# 1_uC.net
KiCad netlist of a schematic drawn in Altium Designer
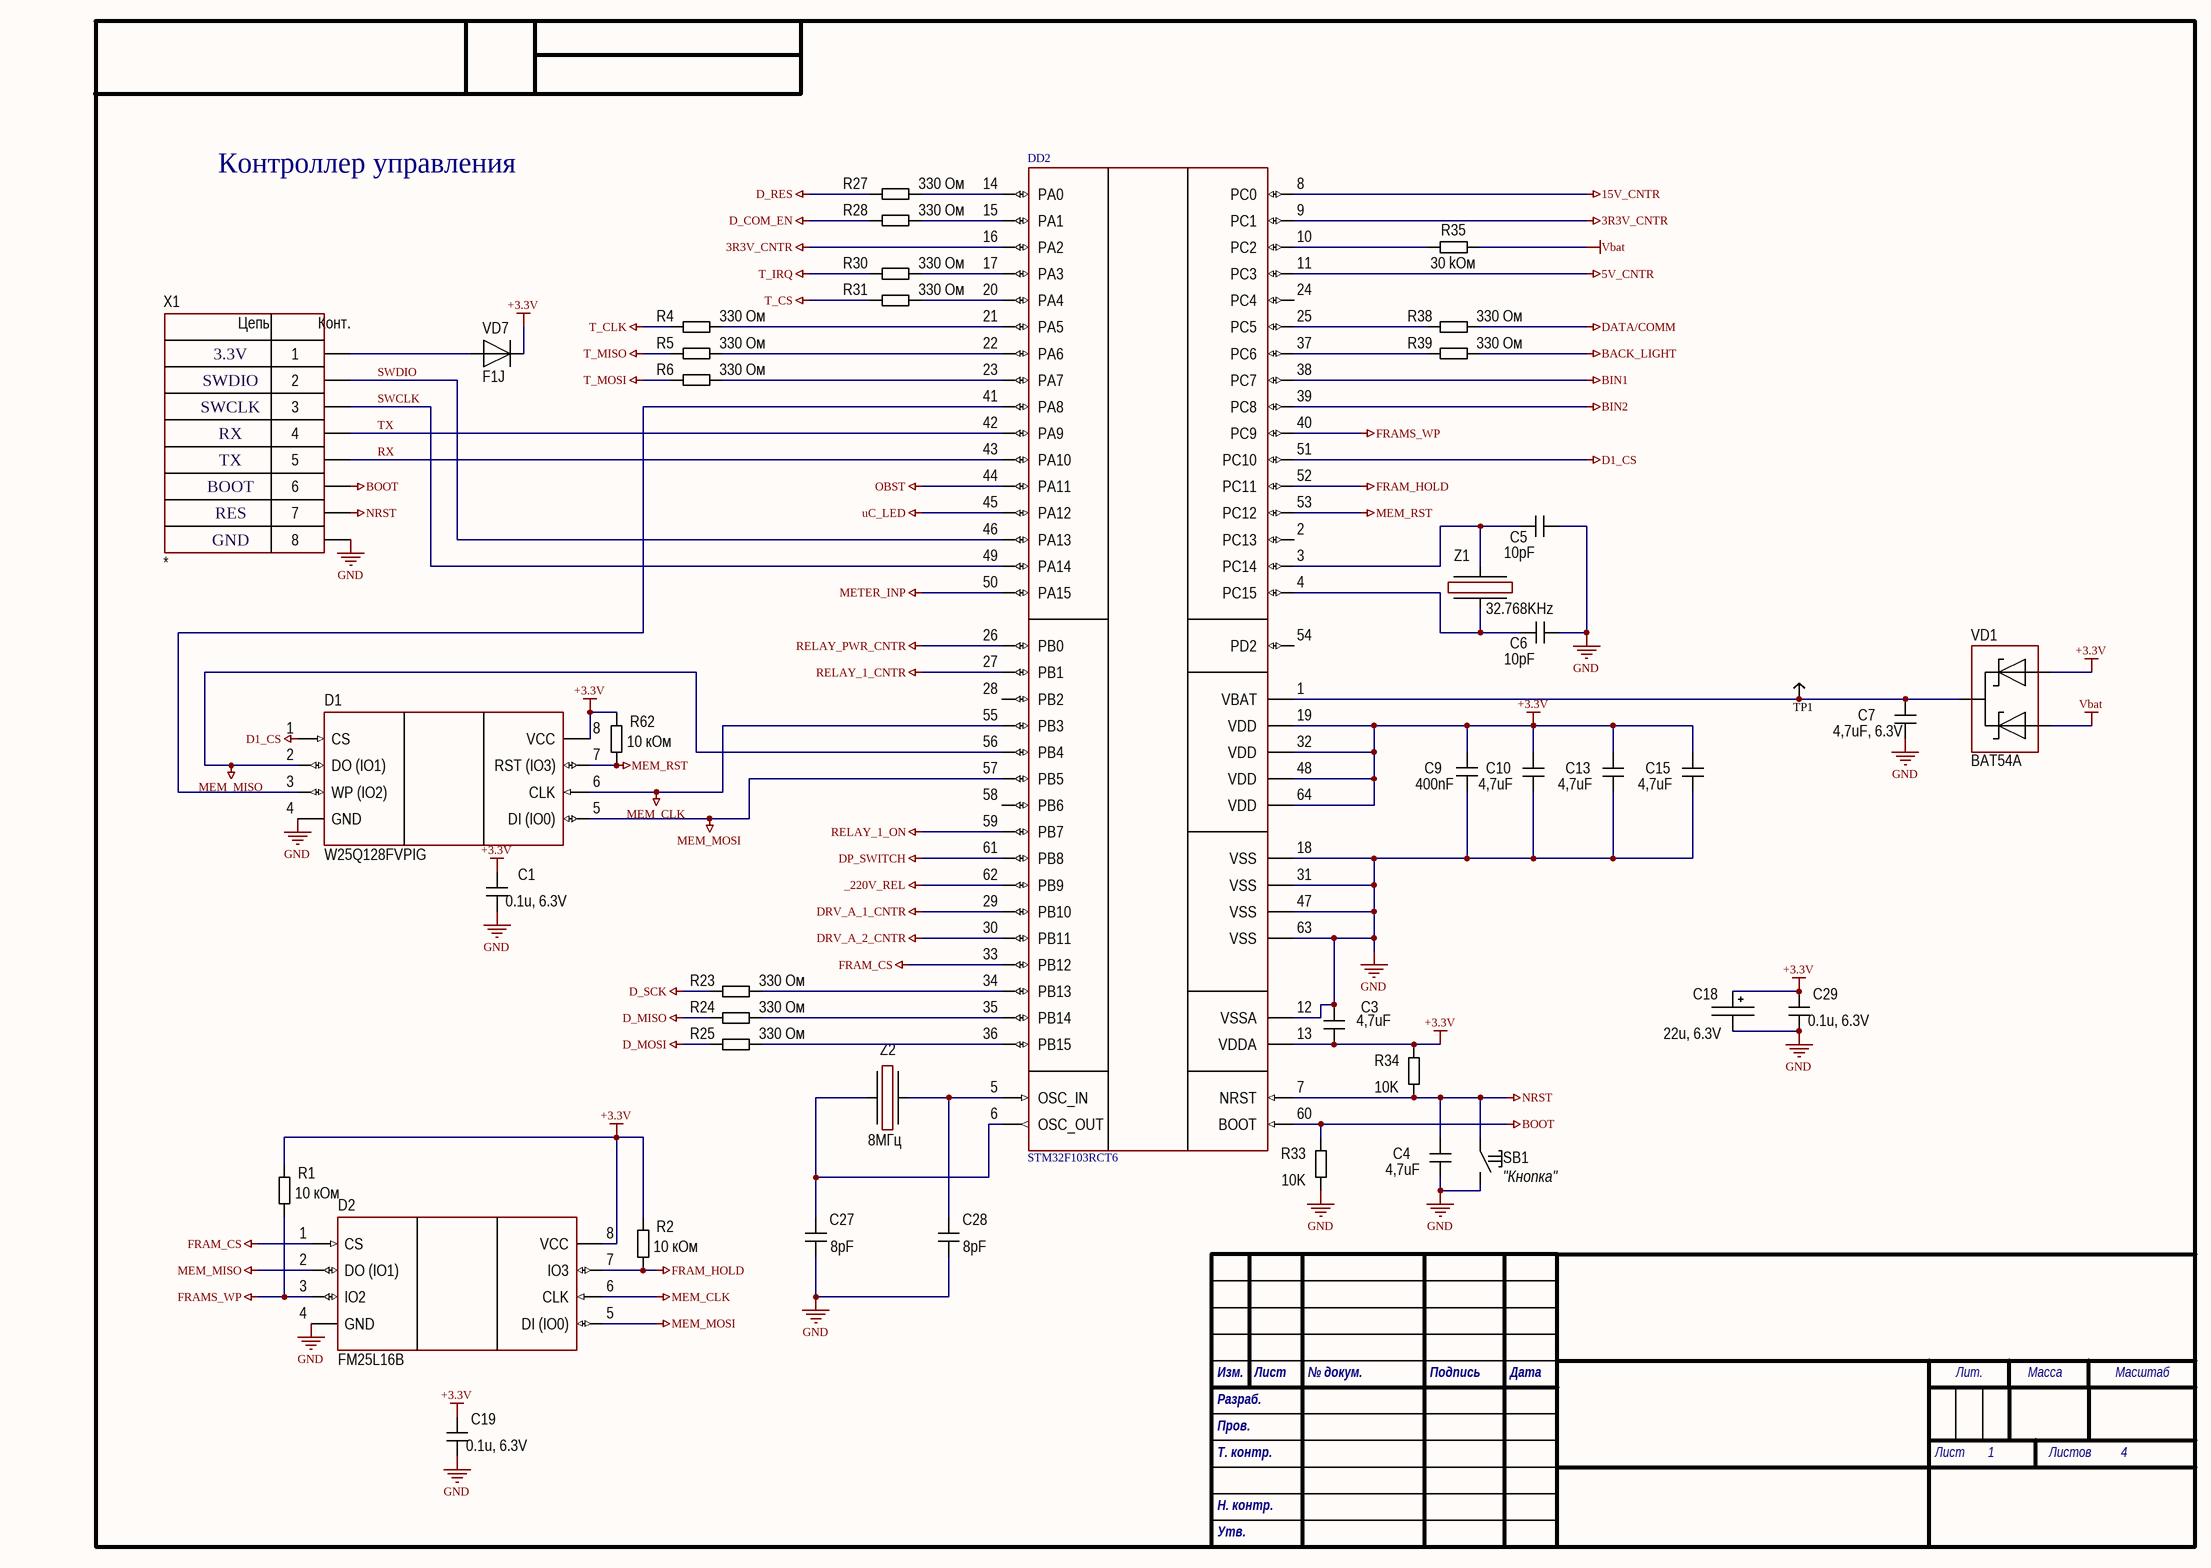
[diagram p0: 1_uC.SchDoc]

(export (version "E")
  (design (tool "Eeschema 10.0.6"))
  (components
    (comp (ref "C1")
      (value "0.1u, 6.3V")
      (footprint "CH0402C")
      (libsource (lib "Condensators") (part "Capacitor"))
    )
    (comp (ref "C3")
      (value "4,7uF")
      (footprint "CH0402C")
      (description "0402")
      (libsource (lib "Condensators") (part "Capacitor"))
    )
    (comp (ref "C4")
      (value "4,7uF")
      (footprint "CH0402C")
      (description "0402")
      (libsource (lib "Condensators") (part "Capacitor"))
    )
    (comp (ref "C5")
      (value "10pF")
      (footprint "CH0402C")
      (description "0402")
      (libsource (lib "Condensators") (part "Capacitor"))
    )
    (comp (ref "C6")
      (value "10pF")
      (footprint "CH0402C")
      (description "0402")
      (libsource (lib "Condensators") (part "Capacitor"))
    )
    (comp (ref "C7")
      (value "4,7uF, 6.3V")
      (footprint "CH0402C")
      (libsource (lib "Condensators") (part "Capacitor"))
    )
    (comp (ref "C9")
      (value "400nF")
      (footprint "CH0402C")
      (description "0402")
      (libsource (lib "Condensators") (part "Capacitor"))
    )
    (comp (ref "C10")
      (value "4,7uF")
      (footprint "CH0402C")
      (description "0402")
      (libsource (lib "Condensators") (part "Capacitor"))
    )
    (comp (ref "C13")
      (value "4,7uF")
      (footprint "CH0402C")
      (description "0402")
      (libsource (lib "Condensators") (part "Capacitor"))
    )
    (comp (ref "C15")
      (value "4,7uF")
      (footprint "CH0402C")
      (description "0402")
      (libsource (lib "Condensators") (part "Capacitor"))
    )
    (comp (ref "C18")
      (value "22u, 6.3V")
      (footprint "TANTAL_A")
      (libsource (lib "Condensators") (part "TantalCap"))
    )
    (comp (ref "C19")
      (value "0.1u, 6.3V")
      (footprint "CH0402C")
      (libsource (lib "Condensators") (part "Capacitor"))
    )
    (comp (ref "C27")
      (value "8pF")
      (footprint "CH0402C")
      (description "0402")
      (libsource (lib "Condensators") (part "Capacitor"))
    )
    (comp (ref "C28")
      (value "8pF")
      (footprint "CH0402C")
      (description "0402")
      (libsource (lib "Condensators") (part "Capacitor"))
    )
    (comp (ref "C29")
      (value "0.1u, 6.3V")
      (footprint "CH0402C")
      (libsource (lib "Condensators") (part "Capacitor"))
    )
    (comp (ref "D1")
      (value "W25Q128FVPIG")
      (footprint "8-WSON (5x6mm)without_holes")
      (description "Flash")
      (fields (field (name "MANUFACTURER") "Winbond Electronics"))
      (libsource (lib "MicroIC") (part "W25Q128FVPIG"))
    )
    (comp (ref "D2")
      (value "FM25L16B")
      (footprint "8-SOIC")
      (description "Flash")
      (fields (field (name "MANUFACTURER") "Winbond Electronics"))
      (libsource (lib "MicroIC") (part "W25Q80JVSSIQ"))
    )
    (comp (ref "DD2")
      (value "STM32F103RCT6")
      (footprint "64-LQFP")
      (description "Cortex-M3 (64-LQFP)")
      (libsource (lib "MicroIC") (part "STM32F103RCT6"))
    )
    (comp (ref "R1")
      (value "10 кОм")
      (footprint "CH0402R")
      (description "0603")
      (libsource (lib "Resistors") (part "Resistor"))
    )
    (comp (ref "R2")
      (value "10 кОм")
      (footprint "CH0402R")
      (description "0603")
      (libsource (lib "Resistors") (part "Resistor"))
    )
    (comp (ref "R4")
      (value "330 Ом")
      (footprint "CH0402R")
      (description "0603")
      (libsource (lib "Resistors") (part "Resistor"))
    )
    (comp (ref "R5")
      (value "330 Ом")
      (footprint "CH0402R")
      (description "0603")
      (libsource (lib "Resistors") (part "Resistor"))
    )
    (comp (ref "R6")
      (value "330 Ом")
      (footprint "CH0402R")
      (description "0603")
      (libsource (lib "Resistors") (part "Resistor"))
    )
    (comp (ref "R23")
      (value "330 Ом")
      (footprint "CH0402R")
      (description "0603")
      (libsource (lib "Resistors") (part "Resistor"))
    )
    (comp (ref "R24")
      (value "330 Ом")
      (footprint "CH0402R")
      (description "0603")
      (libsource (lib "Resistors") (part "Resistor"))
    )
    (comp (ref "R25")
      (value "330 Ом")
      (footprint "CH0402R")
      (description "0603")
      (libsource (lib "Resistors") (part "Resistor"))
    )
    (comp (ref "R27")
      (value "330 Ом")
      (footprint "CH0402R")
      (description "0603")
      (libsource (lib "Resistors") (part "Resistor"))
    )
    (comp (ref "R28")
      (value "330 Ом")
      (footprint "CH0402R")
      (description "0603")
      (libsource (lib "Resistors") (part "Resistor"))
    )
    (comp (ref "R30")
      (value "330 Ом")
      (footprint "CH0402R")
      (description "0603")
      (libsource (lib "Resistors") (part "Resistor"))
    )
    (comp (ref "R31")
      (value "330 Ом")
      (footprint "CH0402R")
      (description "0603")
      (libsource (lib "Resistors") (part "Resistor"))
    )
    (comp (ref "R33")
      (value "10K")
      (footprint "CH0402R")
      (description "0805")
      (libsource (lib "Resistors") (part "Resistor"))
    )
    (comp (ref "R34")
      (value "10K")
      (footprint "CH0402R")
      (description "0805")
      (libsource (lib "Resistors") (part "Resistor"))
    )
    (comp (ref "R35")
      (value "30 kОм")
      (footprint "CH0402R")
      (description "0603")
      (libsource (lib "Resistors") (part "Resistor"))
    )
    (comp (ref "R38")
      (value "330 Ом")
      (footprint "CH0402R")
      (description "0603")
      (libsource (lib "Resistors") (part "Resistor"))
    )
    (comp (ref "R39")
      (value "330 Ом")
      (footprint "CH0402R")
      (description "0603")
      (libsource (lib "Resistors") (part "Resistor"))
    )
    (comp (ref "R62")
      (value "10 кОм")
      (footprint "CH0402R")
      (description "0603")
      (libsource (lib "Resistors") (part "Resistor"))
    )
    (comp (ref "SB1")
      (value "\"Кнопка\"")
      (footprint "TL1014BF160QG")
      (description "6x6 mm")
      (libsource (lib "Connectors") (part "Tactile switches"))
    )
    (comp (ref "TP1") (value "~") (footprint "TestPoint") (libsource (lib "Melochi") (part "TestPoint")))
    (comp (ref "VD1")
      (value "BAT54A")
      (footprint "SOT23_123")
      (description "SOT-23")
      (libsource (lib "Diods") (part "Diod Schottky Array v.1"))
    )
    (comp (ref "VD7") (value "F1J") (footprint "SOD123F") (libsource (lib "Diods") (part "Diod")))
    (comp (ref "X1")
      (value "*")
      (footprint "CON: PBS-8")
      (description "Pin header 8")
      (libsource (lib "Connectors") (part "8-Connector"))
    )
    (comp (ref "Z1") (value "32.768KHz") (footprint "OSC: 3215") (libsource (lib "") (part "Oscillator_1")))
    (comp (ref "Z2")
      (value "8МГц")
      (footprint "OSC: ABM3")
      (description "NX5032GA-8MHz")
      (libsource (lib "Melochi") (part "Oscillator"))
    )
  )
  (nets
    (net (code "1") (name "+3.3V") (class "Default")
      (node (ref "C1") (pin "2") (pinfunction "2_2") (pintype "passive"))
      (node (ref "C10") (pin "2") (pinfunction "2_2") (pintype "passive"))
      (node (ref "C13") (pin "2") (pinfunction "2_2") (pintype "passive"))
      (node (ref "C15") (pin "2") (pinfunction "2_2") (pintype "passive"))
      (node (ref "C18") (pin "1") (pinfunction "1_1") (pintype "power_in"))
      (node (ref "C19") (pin "2") (pinfunction "2_2") (pintype "passive"))
      (node (ref "C29") (pin "2") (pinfunction "2_2") (pintype "passive"))
      (node (ref "C3") (pin "1") (pinfunction "1_1") (pintype "passive"))
      (node (ref "C9") (pin "1") (pinfunction "1_1") (pintype "passive"))
      (node (ref "D1") (pin "8") (pinfunction "VCC_8") (pintype "power_in"))
      (node (ref "D2") (pin "8") (pinfunction "VCC_8") (pintype "power_in"))
      (node (ref "DD2") (pin "13") (pinfunction "VDDA_13") (pintype "power_in"))
      (node (ref "DD2") (pin "19") (pinfunction "VDD_19") (pintype "power_in"))
      (node (ref "DD2") (pin "32") (pinfunction "VDD_32") (pintype "power_in"))
      (node (ref "DD2") (pin "48") (pinfunction "VDD_48") (pintype "power_in"))
      (node (ref "DD2") (pin "64") (pinfunction "VDD_64") (pintype "power_in"))
      (node (ref "R1") (pin "2") (pinfunction "2_2") (pintype "passive"))
      (node (ref "R2") (pin "2") (pinfunction "2_2") (pintype "passive"))
      (node (ref "R34") (pin "2") (pinfunction "2_2") (pintype "passive"))
      (node (ref "R62") (pin "2") (pinfunction "2_2") (pintype "passive"))
      (node (ref "VD1") (pin "1") (pinfunction "1_1") (pintype "passive"))
      (node (ref "VD7") (pin "2") (pinfunction "2_2") (pintype "passive"))
    )
    (net (code "2") (name "/RX") (class "Default")
      (node (ref "DD2") (pin "43") (pinfunction "PA10_43") (pintype "bidirectional"))
      (node (ref "X1") (pin "5") (pinfunction "5_5") (pintype "power_in"))
    )
    (net (code "3") (name "/SWCLK") (class "Default")
      (node (ref "DD2") (pin "49") (pinfunction "PA14_49") (pintype "bidirectional"))
      (node (ref "X1") (pin "3") (pinfunction "3_3") (pintype "power_in"))
    )
    (net (code "4") (name "/SWDIO") (class "Default")
      (node (ref "DD2") (pin "46") (pinfunction "PA13_46") (pintype "bidirectional"))
      (node (ref "X1") (pin "2") (pinfunction "2_2") (pintype "passive"))
    )
    (net (code "5") (name "/TX") (class "Default")
      (node (ref "DD2") (pin "42") (pinfunction "PA9_42") (pintype "bidirectional"))
      (node (ref "X1") (pin "4") (pinfunction "4_4") (pintype "power_in"))
    )
    (net (code "6") (name "3R3V_CNTR") (class "Default")
      (node (ref "DD2") (pin "16") (pinfunction "PA2_16") (pintype "bidirectional"))
      (node (ref "DD2") (pin "9") (pinfunction "PC1_9") (pintype "bidirectional"))
    )
    (net (code "7") (name "5V_CNTR") (class "Default")
      (node (ref "DD2") (pin "11") (pinfunction "PC3_11") (pintype "bidirectional"))
    )
    (net (code "8") (name "15V_CNTR") (class "Default")
      (node (ref "DD2") (pin "8") (pinfunction "PC0_8") (pintype "bidirectional"))
    )
    (net (code "9") (name "BACK_LIGHT") (class "Default")
      (node (ref "R39") (pin "1") (pinfunction "1_1") (pintype "passive"))
    )
    (net (code "10") (name "BIN1") (class "Default")
      (node (ref "DD2") (pin "38") (pinfunction "PC7_38") (pintype "bidirectional"))
    )
    (net (code "11") (name "BIN2") (class "Default")
      (node (ref "DD2") (pin "39") (pinfunction "PC8_39") (pintype "bidirectional"))
    )
    (net (code "12") (name "BOOT") (class "Default")
      (node (ref "DD2") (pin "60") (pinfunction "BOOT_60") (pintype "input"))
      (node (ref "R33") (pin "2") (pinfunction "2_2") (pintype "passive"))
      (node (ref "X1") (pin "6") (pinfunction "6_6") (pintype "power_in"))
    )
    (net (code "13") (name "D1_CS") (class "Default")
      (node (ref "D1") (pin "1") (pinfunction "CS_1") (pintype "input"))
      (node (ref "DD2") (pin "51") (pinfunction "PC10_51") (pintype "bidirectional"))
    )
    (net (code "14") (name "DATA{slash}COMM") (class "Default")
      (node (ref "R38") (pin "1") (pinfunction "1_1") (pintype "passive"))
    )
    (net (code "15") (name "DP_SWITCH") (class "Default")
      (node (ref "DD2") (pin "61") (pinfunction "PB8_61") (pintype "bidirectional"))
    )
    (net (code "16") (name "DRV_A_1_CNTR") (class "Default")
      (node (ref "DD2") (pin "29") (pinfunction "PB10_29") (pintype "bidirectional"))
    )
    (net (code "17") (name "DRV_A_2_CNTR") (class "Default")
      (node (ref "DD2") (pin "30") (pinfunction "PB11_30") (pintype "bidirectional"))
    )
    (net (code "18") (name "D_COM_EN") (class "Default")
      (node (ref "R28") (pin "1") (pinfunction "1_1") (pintype "passive"))
    )
    (net (code "19") (name "D_MISO") (class "Default")
      (node (ref "R24") (pin "1") (pinfunction "1_1") (pintype "passive"))
    )
    (net (code "20") (name "D_MOSI") (class "Default")
      (node (ref "R25") (pin "1") (pinfunction "1_1") (pintype "passive"))
    )
    (net (code "21") (name "D_RES") (class "Default")
      (node (ref "R27") (pin "1") (pinfunction "1_1") (pintype "passive"))
    )
    (net (code "22") (name "D_SCK") (class "Default")
      (node (ref "R23") (pin "1") (pinfunction "1_1") (pintype "passive"))
    )
    (net (code "23") (name "FRAMS_WP") (class "Default")
      (node (ref "D2") (pin "3") (pinfunction "IO2_3") (pintype "bidirectional"))
      (node (ref "DD2") (pin "40") (pinfunction "PC9_40") (pintype "bidirectional"))
      (node (ref "R1") (pin "1") (pinfunction "1_1") (pintype "passive"))
    )
    (net (code "24") (name "FRAM_CS") (class "Default")
      (node (ref "D2") (pin "1") (pinfunction "CS_1") (pintype "input"))
      (node (ref "DD2") (pin "33") (pinfunction "PB12_33") (pintype "bidirectional"))
    )
    (net (code "25") (name "FRAM_HOLD") (class "Default")
      (node (ref "D2") (pin "7") (pinfunction "IO3_7") (pintype "bidirectional"))
      (node (ref "DD2") (pin "52") (pinfunction "PC11_52") (pintype "bidirectional"))
      (node (ref "R2") (pin "1") (pinfunction "1_1") (pintype "passive"))
    )
    (net (code "26") (name "GND") (class "Default")
      (node (ref "C1") (pin "1") (pinfunction "1_1") (pintype "passive"))
      (node (ref "C10") (pin "1") (pinfunction "1_1") (pintype "passive"))
      (node (ref "C13") (pin "1") (pinfunction "1_1") (pintype "passive"))
      (node (ref "C15") (pin "1") (pinfunction "1_1") (pintype "passive"))
      (node (ref "C18") (pin "2") (pinfunction "2_2") (pintype "power_in"))
      (node (ref "C19") (pin "1") (pinfunction "1_1") (pintype "passive"))
      (node (ref "C27") (pin "1") (pinfunction "1_1") (pintype "passive"))
      (node (ref "C28") (pin "1") (pinfunction "1_1") (pintype "passive"))
      (node (ref "C29") (pin "1") (pinfunction "1_1") (pintype "passive"))
      (node (ref "C3") (pin "2") (pinfunction "2_2") (pintype "passive"))
      (node (ref "C4") (pin "1") (pinfunction "1_1") (pintype "passive"))
      (node (ref "C5") (pin "2") (pinfunction "2_2") (pintype "passive"))
      (node (ref "C6") (pin "1") (pinfunction "1_1") (pintype "passive"))
      (node (ref "C7") (pin "1") (pinfunction "1_1") (pintype "passive"))
      (node (ref "C9") (pin "2") (pinfunction "2_2") (pintype "passive"))
      (node (ref "D1") (pin "4") (pinfunction "GND_4") (pintype "power_in"))
      (node (ref "D2") (pin "4") (pinfunction "GND_4") (pintype "power_in"))
      (node (ref "DD2") (pin "12") (pinfunction "VSSA_12") (pintype "power_in"))
      (node (ref "DD2") (pin "18") (pinfunction "VSS_18") (pintype "power_in"))
      (node (ref "DD2") (pin "31") (pinfunction "VSS_31") (pintype "power_in"))
      (node (ref "DD2") (pin "47") (pinfunction "VSS_47") (pintype "power_in"))
      (node (ref "DD2") (pin "63") (pinfunction "VSS_63") (pintype "power_in"))
      (node (ref "R33") (pin "1") (pinfunction "1_1") (pintype "passive"))
      (node (ref "SB1") (pin "2") (pinfunction "2_2") (pintype "passive"))
      (node (ref "X1") (pin "8") (pinfunction "8_8") (pintype "power_in"))
    )
    (net (code "27") (name "MEM_CLK") (class "Default")
      (node (ref "D1") (pin "6") (pinfunction "CLK_6") (pintype "input"))
      (node (ref "D2") (pin "6") (pinfunction "CLK_6") (pintype "input"))
      (node (ref "DD2") (pin "55") (pinfunction "PB3_55") (pintype "bidirectional"))
    )
    (net (code "28") (name "MEM_MISO") (class "Default")
      (node (ref "D1") (pin "2") (pinfunction "DO_(IO1)_2") (pintype "bidirectional"))
      (node (ref "D2") (pin "2") (pinfunction "DO_(IO1)_2") (pintype "bidirectional"))
      (node (ref "DD2") (pin "56") (pinfunction "PB4_56") (pintype "bidirectional"))
    )
    (net (code "29") (name "MEM_MOSI") (class "Default")
      (node (ref "D1") (pin "5") (pinfunction "DI_(IO0)_5") (pintype "bidirectional"))
      (node (ref "D2") (pin "5") (pinfunction "DI_(IO0)_5") (pintype "bidirectional"))
      (node (ref "DD2") (pin "57") (pinfunction "PB5_57") (pintype "bidirectional"))
    )
    (net (code "30") (name "MEM_RST") (class "Default")
      (node (ref "D1") (pin "7") (pinfunction "RST_(IO3)_7") (pintype "bidirectional"))
      (node (ref "DD2") (pin "53") (pinfunction "PC12_53") (pintype "bidirectional"))
      (node (ref "R62") (pin "1") (pinfunction "1_1") (pintype "passive"))
    )
    (net (code "31") (name "METER_INP") (class "Default")
      (node (ref "DD2") (pin "50") (pinfunction "PA15_50") (pintype "bidirectional"))
    )
    (net (code "32") (name "NRST") (class "Default")
      (node (ref "C4") (pin "2") (pinfunction "2_2") (pintype "passive"))
      (node (ref "DD2") (pin "7") (pinfunction "NRST_7") (pintype "input"))
      (node (ref "R34") (pin "1") (pinfunction "1_1") (pintype "passive"))
      (node (ref "SB1") (pin "1") (pinfunction "1_1") (pintype "passive"))
      (node (ref "X1") (pin "7") (pinfunction "7_7") (pintype "power_in"))
    )
    (net (code "33") (name "Net-(D1-WP_(IO2))") (class "Default")
      (node (ref "D1") (pin "3") (pinfunction "WP_(IO2)_3") (pintype "bidirectional"))
      (node (ref "DD2") (pin "41") (pinfunction "PA8_41") (pintype "bidirectional"))
    )
    (net (code "34") (name "Net-(DD2-OSC_IN)") (class "Default")
      (node (ref "C28") (pin "2") (pinfunction "2_2") (pintype "passive"))
      (node (ref "DD2") (pin "5") (pinfunction "OSC_IN_5") (pintype "input"))
      (node (ref "Z2") (pin "3") (pinfunction "3_3") (pintype "passive"))
    )
    (net (code "35") (name "Net-(DD2-OSC_OUT)") (class "Default")
      (node (ref "C27") (pin "2") (pinfunction "2_2") (pintype "passive"))
      (node (ref "DD2") (pin "6") (pinfunction "OSC_OUT_6") (pintype "output"))
      (node (ref "Z2") (pin "1") (pinfunction "1_1") (pintype "passive"))
    )
    (net (code "36") (name "Net-(DD2-PA0)") (class "Default")
      (node (ref "DD2") (pin "14") (pinfunction "PA0_14") (pintype "bidirectional"))
      (node (ref "R27") (pin "2") (pinfunction "2_2") (pintype "passive"))
    )
    (net (code "37") (name "Net-(DD2-PA1)") (class "Default")
      (node (ref "DD2") (pin "15") (pinfunction "PA1_15") (pintype "bidirectional"))
      (node (ref "R28") (pin "2") (pinfunction "2_2") (pintype "passive"))
    )
    (net (code "38") (name "Net-(DD2-PA3)") (class "Default")
      (node (ref "DD2") (pin "17") (pinfunction "PA3_17") (pintype "bidirectional"))
      (node (ref "R30") (pin "2") (pinfunction "2_2") (pintype "passive"))
    )
    (net (code "39") (name "Net-(DD2-PA4)") (class "Default")
      (node (ref "DD2") (pin "20") (pinfunction "PA4_20") (pintype "bidirectional"))
      (node (ref "R31") (pin "2") (pinfunction "2_2") (pintype "passive"))
    )
    (net (code "40") (name "Net-(DD2-PA5)") (class "Default")
      (node (ref "DD2") (pin "21") (pinfunction "PA5_21") (pintype "bidirectional"))
      (node (ref "R4") (pin "2") (pinfunction "2_2") (pintype "passive"))
    )
    (net (code "41") (name "Net-(DD2-PA6)") (class "Default")
      (node (ref "DD2") (pin "22") (pinfunction "PA6_22") (pintype "bidirectional"))
      (node (ref "R5") (pin "2") (pinfunction "2_2") (pintype "passive"))
    )
    (net (code "42") (name "Net-(DD2-PA7)") (class "Default")
      (node (ref "DD2") (pin "23") (pinfunction "PA7_23") (pintype "bidirectional"))
      (node (ref "R6") (pin "2") (pinfunction "2_2") (pintype "passive"))
    )
    (net (code "43") (name "Net-(DD2-PB13)") (class "Default")
      (node (ref "DD2") (pin "34") (pinfunction "PB13_34") (pintype "bidirectional"))
      (node (ref "R23") (pin "2") (pinfunction "2_2") (pintype "passive"))
    )
    (net (code "44") (name "Net-(DD2-PB14)") (class "Default")
      (node (ref "DD2") (pin "35") (pinfunction "PB14_35") (pintype "bidirectional"))
      (node (ref "R24") (pin "2") (pinfunction "2_2") (pintype "passive"))
    )
    (net (code "45") (name "Net-(DD2-PB15)") (class "Default")
      (node (ref "DD2") (pin "36") (pinfunction "PB15_36") (pintype "bidirectional"))
      (node (ref "R25") (pin "2") (pinfunction "2_2") (pintype "passive"))
    )
    (net (code "46") (name "Net-(DD2-PC2)") (class "Default")
      (node (ref "DD2") (pin "10") (pinfunction "PC2_10") (pintype "bidirectional"))
      (node (ref "R35") (pin "2") (pinfunction "2_2") (pintype "passive"))
    )
    (net (code "47") (name "Net-(DD2-PC5)") (class "Default")
      (node (ref "DD2") (pin "25") (pinfunction "PC5_25") (pintype "bidirectional"))
      (node (ref "R38") (pin "2") (pinfunction "2_2") (pintype "passive"))
    )
    (net (code "48") (name "Net-(DD2-PC6)") (class "Default")
      (node (ref "DD2") (pin "37") (pinfunction "PC6_37") (pintype "bidirectional"))
      (node (ref "R39") (pin "2") (pinfunction "2_2") (pintype "passive"))
    )
    (net (code "49") (name "Net-(DD2-PC14)") (class "Default")
      (node (ref "C5") (pin "1") (pinfunction "1_1") (pintype "passive"))
      (node (ref "DD2") (pin "3") (pinfunction "PC14_3") (pintype "bidirectional"))
      (node (ref "Z1") (pin "3") (pinfunction "3_3") (pintype "passive"))
    )
    (net (code "50") (name "Net-(DD2-PC15)") (class "Default")
      (node (ref "C6") (pin "2") (pinfunction "2_2") (pintype "passive"))
      (node (ref "DD2") (pin "4") (pinfunction "PC15_4") (pintype "bidirectional"))
      (node (ref "Z1") (pin "1") (pinfunction "1_1") (pintype "passive"))
    )
    (net (code "51") (name "Net-(DD2-VBAT)") (class "Default")
      (node (ref "C7") (pin "2") (pinfunction "2_2") (pintype "passive"))
      (node (ref "DD2") (pin "1") (pinfunction "VBAT_1") (pintype "power_in"))
      (node (ref "TP1") (pin "0") (pinfunction "0_0") (pintype "passive"))
      (node (ref "VD1") (pin "2") (pinfunction "2_2") (pintype "passive"))
    )
    (net (code "52") (name "Net-(VD7-Pad1)") (class "Default")
      (node (ref "VD7") (pin "1") (pinfunction "1_1") (pintype "passive"))
      (node (ref "X1") (pin "1") (pinfunction "1_1") (pintype "passive"))
    )
    (net (code "53") (name "OBST") (class "Default")
      (node (ref "DD2") (pin "44") (pinfunction "PA11_44") (pintype "bidirectional"))
    )
    (net (code "54") (name "RELAY_1_CNTR") (class "Default")
      (node (ref "DD2") (pin "27") (pinfunction "PB1_27") (pintype "bidirectional"))
    )
    (net (code "55") (name "RELAY_1_ON") (class "Default")
      (node (ref "DD2") (pin "59") (pinfunction "PB7_59") (pintype "bidirectional"))
    )
    (net (code "56") (name "RELAY_PWR_CNTR") (class "Default")
      (node (ref "DD2") (pin "26") (pinfunction "PB0_26") (pintype "bidirectional"))
    )
    (net (code "57") (name "T_CLK") (class "Default")
      (node (ref "R4") (pin "1") (pinfunction "1_1") (pintype "passive"))
    )
    (net (code "58") (name "T_CS") (class "Default")
      (node (ref "R31") (pin "1") (pinfunction "1_1") (pintype "passive"))
    )
    (net (code "59") (name "T_IRQ") (class "Default")
      (node (ref "R30") (pin "1") (pinfunction "1_1") (pintype "passive"))
    )
    (net (code "60") (name "T_MISO") (class "Default")
      (node (ref "R5") (pin "1") (pinfunction "1_1") (pintype "passive"))
    )
    (net (code "61") (name "T_MOSI") (class "Default")
      (node (ref "R6") (pin "1") (pinfunction "1_1") (pintype "passive"))
    )
    (net (code "62") (name "Vbat") (class "Default")
      (node (ref "R35") (pin "1") (pinfunction "1_1") (pintype "passive"))
      (node (ref "VD1") (pin "3") (pinfunction "3_3") (pintype "passive"))
    )
    (net (code "63") (name "_220V_REL") (class "Default")
      (node (ref "DD2") (pin "62") (pinfunction "PB9_62") (pintype "bidirectional"))
    )
    (net (code "64") (name "uC_LED") (class "Default")
      (node (ref "DD2") (pin "45") (pinfunction "PA12_45") (pintype "bidirectional"))
    )
    (net (code "65") (name "unconnected-(DD2-PB2-Pad28)") (class "Default")
      (node (ref "DD2") (pin "28") (pinfunction "PB2_28") (pintype "bidirectional"))
    )
    (net (code "66") (name "unconnected-(DD2-PB6-Pad58)") (class "Default")
      (node (ref "DD2") (pin "58") (pinfunction "PB6_58") (pintype "bidirectional"))
    )
    (net (code "67") (name "unconnected-(DD2-PC4-Pad24)") (class "Default")
      (node (ref "DD2") (pin "24") (pinfunction "PC4_24") (pintype "bidirectional"))
    )
    (net (code "68") (name "unconnected-(DD2-PC13-Pad2)") (class "Default")
      (node (ref "DD2") (pin "2") (pinfunction "PC13_2") (pintype "bidirectional"))
    )
    (net (code "69") (name "unconnected-(DD2-PD2-Pad54)") (class "Default")
      (node (ref "DD2") (pin "54") (pinfunction "PD2_54") (pintype "bidirectional"))
    )
  )
)
